# 07_COMM_BOARD.net
KiCad netlist of a schematic drawn in Altium Designer
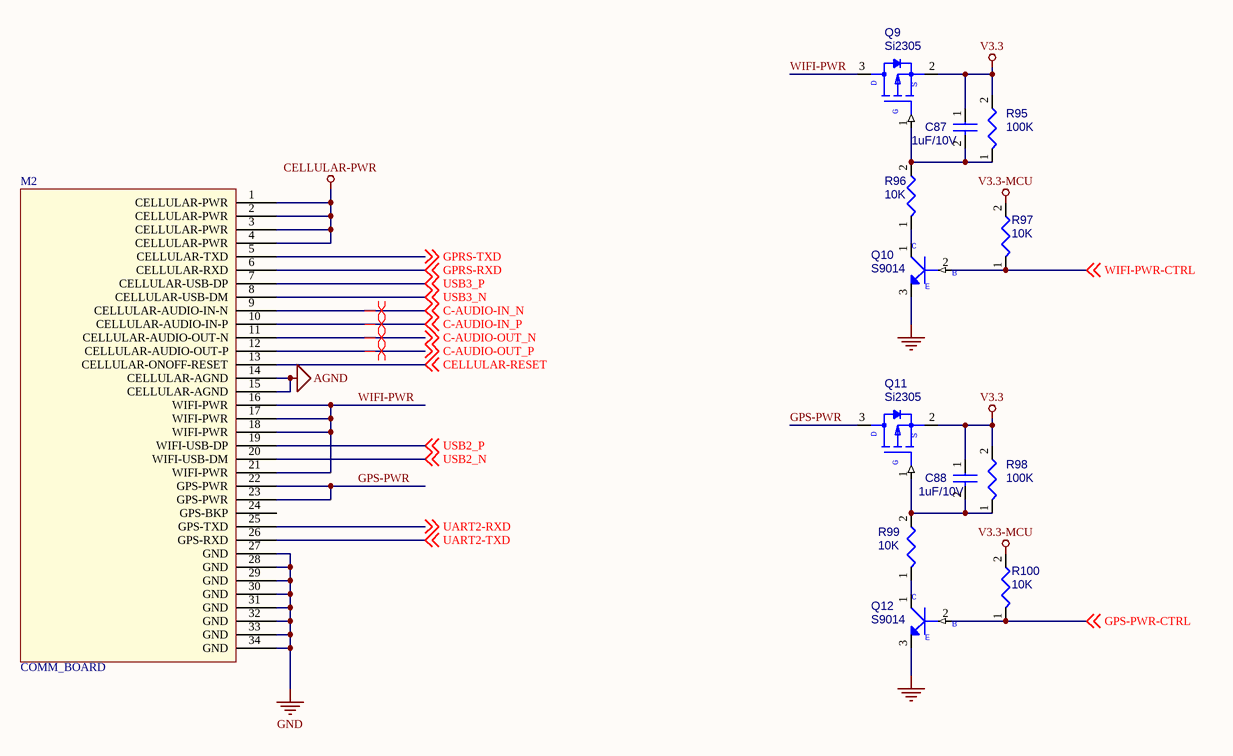
[diagram p0: [07]COMM_BOARD.SchDoc]

(export (version "E")
  (design (tool "Eeschema 10.0.6"))
  (components
    (comp (ref "C87") (value "1uF/10V") (libsource (lib "*") (part "P_CAP NP")))
    (comp (ref "C88") (value "1uF/10V") (libsource (lib "*") (part "P_CAP NP")))
    (comp (ref "M2") (value "COMM_BOARD") (libsource (lib "Schlib") (part "COMM_BOARD")))
    (comp (ref "Q9")
      (value "Si2305")
      (footprint "MOSFET")
      (fields (field (name "PART NUMBER") "SB934010010"))
      (libsource (lib "*") (part "AO3401L_SOT23-3_0"))
    )
    (comp (ref "Q10")
      (value "S9014")
      (footprint "NPN")
      (fields (field (name "PART NUMBER") "SB039040000"))
      (libsource (lib "*") (part "MMBT3904_NL_SOT23-3"))
    )
    (comp (ref "Q11")
      (value "Si2305")
      (footprint "MOSFET")
      (fields (field (name "PART NUMBER") "SB934010010"))
      (libsource (lib "*") (part "AO3401L_SOT23-3_0"))
    )
    (comp (ref "Q12")
      (value "S9014")
      (footprint "NPN")
      (fields (field (name "PART NUMBER") "SB039040000"))
      (libsource (lib "*") (part "MMBT3904_NL_SOT23-3"))
    )
    (comp (ref "R95")
      (value "100K")
      (footprint "0603")
      (fields (field (name "PART NUMBER") "SD013100A8L") (field (name "OEM PART NUMBER") "F9"))
      (libsource (lib "*") (part "P_R"))
    )
    (comp (ref "R96")
      (value "10K")
      (footprint "0603")
      (fields (field (name "PART NUMBER") "SD013100A8L") (field (name "OEM PART NUMBER") "F9"))
      (libsource (lib "*") (part "P_R"))
    )
    (comp (ref "R97") (value "10K") (libsource (lib "*") (part "R_Dup1")))
    (comp (ref "R98")
      (value "100K")
      (footprint "0603")
      (fields (field (name "PART NUMBER") "SD013100A8L") (field (name "OEM PART NUMBER") "F9"))
      (libsource (lib "*") (part "P_R"))
    )
    (comp (ref "R99")
      (value "10K")
      (footprint "0603")
      (fields (field (name "PART NUMBER") "SD013100A8L") (field (name "OEM PART NUMBER") "F9"))
      (libsource (lib "*") (part "P_R"))
    )
    (comp (ref "R100") (value "10K") (libsource (lib "*") (part "R_Dup1")))
  )
  (nets
    (net (code "1") (name "/GPS-PWR") (class "Default")
      (node (ref "M2") (pin "22") (pinfunction "GPS-PWR_22") (pintype "passive"))
      (node (ref "M2") (pin "23") (pinfunction "GPS-PWR_23") (pintype "passive"))
      (node (ref "Q11") (pin "3") (pinfunction "D_3") (pintype "passive"))
    )
    (net (code "2") (name "/WIFI-PWR") (class "Default")
      (node (ref "M2") (pin "16") (pinfunction "WIFI-PWR_16") (pintype "passive"))
      (node (ref "M2") (pin "17") (pinfunction "WIFI-PWR_17") (pintype "passive"))
      (node (ref "M2") (pin "18") (pinfunction "WIFI-PWR_18") (pintype "passive"))
      (node (ref "M2") (pin "21") (pinfunction "WIFI-PWR_21") (pintype "passive"))
      (node (ref "Q9") (pin "3") (pinfunction "D_3") (pintype "passive"))
    )
    (net (code "3") (name "AGND") (class "Default")
      (node (ref "M2") (pin "14") (pinfunction "CELLULAR-AGND_14") (pintype "passive"))
      (node (ref "M2") (pin "15") (pinfunction "CELLULAR-AGND_15") (pintype "passive"))
    )
    (net (code "4") (name "C-AUDIO-IN_N") (class "Default")
      (node (ref "M2") (pin "9") (pinfunction "CELLULAR-AUDIO-IN-N_9") (pintype "passive"))
    )
    (net (code "5") (name "C-AUDIO-IN_P") (class "Default")
      (node (ref "M2") (pin "10") (pinfunction "CELLULAR-AUDIO-IN-P_10") (pintype "passive"))
    )
    (net (code "6") (name "C-AUDIO-OUT_N") (class "Default")
      (node (ref "M2") (pin "11") (pinfunction "CELLULAR-AUDIO-OUT-N_11") (pintype "passive"))
    )
    (net (code "7") (name "C-AUDIO-OUT_P") (class "Default")
      (node (ref "M2") (pin "12") (pinfunction "CELLULAR-AUDIO-OUT-P_12") (pintype "passive"))
    )
    (net (code "8") (name "CELLULAR-PWR") (class "Default")
      (node (ref "M2") (pin "1") (pinfunction "CELLULAR-PWR_1") (pintype "passive"))
      (node (ref "M2") (pin "2") (pinfunction "CELLULAR-PWR_2") (pintype "passive"))
      (node (ref "M2") (pin "3") (pinfunction "CELLULAR-PWR_3") (pintype "passive"))
      (node (ref "M2") (pin "4") (pinfunction "CELLULAR-PWR_4") (pintype "passive"))
    )
    (net (code "9") (name "CELLULAR-RESET") (class "Default")
      (node (ref "M2") (pin "13") (pinfunction "CELLULAR-ONOFF-RESET_13") (pintype "passive"))
    )
    (net (code "10") (name "GND") (class "Default")
      (node (ref "M2") (pin "27") (pinfunction "GND_27") (pintype "passive"))
      (node (ref "M2") (pin "28") (pinfunction "GND_28") (pintype "passive"))
      (node (ref "M2") (pin "29") (pinfunction "GND_29") (pintype "passive"))
      (node (ref "M2") (pin "30") (pinfunction "GND_30") (pintype "passive"))
      (node (ref "M2") (pin "31") (pinfunction "GND_31") (pintype "passive"))
      (node (ref "M2") (pin "32") (pinfunction "GND_32") (pintype "passive"))
      (node (ref "M2") (pin "33") (pinfunction "GND_33") (pintype "passive"))
      (node (ref "M2") (pin "34") (pinfunction "GND_34") (pintype "passive"))
      (node (ref "Q10") (pin "3") (pinfunction "EMITTER_3") (pintype "passive"))
      (node (ref "Q12") (pin "3") (pinfunction "EMITTER_3") (pintype "passive"))
    )
    (net (code "11") (name "GPRS-RXD") (class "Default")
      (node (ref "M2") (pin "6") (pinfunction "CELLULAR-RXD_6") (pintype "passive"))
    )
    (net (code "12") (name "GPRS-TXD") (class "Default")
      (node (ref "M2") (pin "5") (pinfunction "CELLULAR-TXD_5") (pintype "passive"))
    )
    (net (code "13") (name "GPS-PWR-CTRL") (class "Default")
      (node (ref "Q12") (pin "2") (pinfunction "BASE_2") (pintype "input"))
      (node (ref "R100") (pin "1") (pinfunction "1_1") (pintype "passive"))
    )
    (net (code "14") (name "Net-(Q9-G)") (class "Default")
      (node (ref "C87") (pin "2") (pinfunction "2_2") (pintype "passive"))
      (node (ref "Q9") (pin "1") (pinfunction "G_1") (pintype "input"))
      (node (ref "R95") (pin "1") (pinfunction "1_1") (pintype "passive"))
      (node (ref "R96") (pin "2") (pinfunction "2_2") (pintype "passive"))
    )
    (net (code "15") (name "Net-(Q10-COLLECTOR)") (class "Default")
      (node (ref "Q10") (pin "1") (pinfunction "COLLECTOR_1") (pintype "passive"))
      (node (ref "R96") (pin "1") (pinfunction "1_1") (pintype "passive"))
    )
    (net (code "16") (name "Net-(Q11-G)") (class "Default")
      (node (ref "C88") (pin "2") (pinfunction "2_2") (pintype "passive"))
      (node (ref "Q11") (pin "1") (pinfunction "G_1") (pintype "input"))
      (node (ref "R98") (pin "1") (pinfunction "1_1") (pintype "passive"))
      (node (ref "R99") (pin "2") (pinfunction "2_2") (pintype "passive"))
    )
    (net (code "17") (name "Net-(Q12-COLLECTOR)") (class "Default")
      (node (ref "Q12") (pin "1") (pinfunction "COLLECTOR_1") (pintype "passive"))
      (node (ref "R99") (pin "1") (pinfunction "1_1") (pintype "passive"))
    )
    (net (code "18") (name "UART2-RXD") (class "Default")
      (node (ref "M2") (pin "25") (pinfunction "GPS-TXD_25") (pintype "passive"))
    )
    (net (code "19") (name "UART2-TXD") (class "Default")
      (node (ref "M2") (pin "26") (pinfunction "GPS-RXD_26") (pintype "passive"))
    )
    (net (code "20") (name "USB2_N") (class "Default")
      (node (ref "M2") (pin "20") (pinfunction "WIFI-USB-DM_20") (pintype "passive"))
    )
    (net (code "21") (name "USB2_P") (class "Default")
      (node (ref "M2") (pin "19") (pinfunction "WIFI-USB-DP_19") (pintype "passive"))
    )
    (net (code "22") (name "USB3_N") (class "Default")
      (node (ref "M2") (pin "8") (pinfunction "CELLULAR-USB-DM_8") (pintype "passive"))
    )
    (net (code "23") (name "USB3_P") (class "Default")
      (node (ref "M2") (pin "7") (pinfunction "CELLULAR-USB-DP_7") (pintype "passive"))
    )
    (net (code "24") (name "V3.3") (class "Default")
      (node (ref "C87") (pin "1") (pinfunction "1_1") (pintype "passive"))
      (node (ref "C88") (pin "1") (pinfunction "1_1") (pintype "passive"))
      (node (ref "Q11") (pin "2") (pinfunction "S_2") (pintype "passive"))
      (node (ref "Q9") (pin "2") (pinfunction "S_2") (pintype "passive"))
      (node (ref "R95") (pin "2") (pinfunction "2_2") (pintype "passive"))
      (node (ref "R98") (pin "2") (pinfunction "2_2") (pintype "passive"))
    )
    (net (code "25") (name "V3.3-MCU") (class "Default")
      (node (ref "R100") (pin "2") (pinfunction "2_2") (pintype "passive"))
      (node (ref "R97") (pin "2") (pinfunction "2_2") (pintype "passive"))
    )
    (net (code "26") (name "WIFI-PWR-CTRL") (class "Default")
      (node (ref "Q10") (pin "2") (pinfunction "BASE_2") (pintype "input"))
      (node (ref "R97") (pin "1") (pinfunction "1_1") (pintype "passive"))
    )
    (net (code "27") (name "unconnected-(M2-GPS-BKP-Pad24)") (class "Default")
      (node (ref "M2") (pin "24") (pinfunction "GPS-BKP_24") (pintype "passive"))
    )
  )
)
